# i2-mb_r1.net
KiCad netlist of a schematic drawn in EAGLE
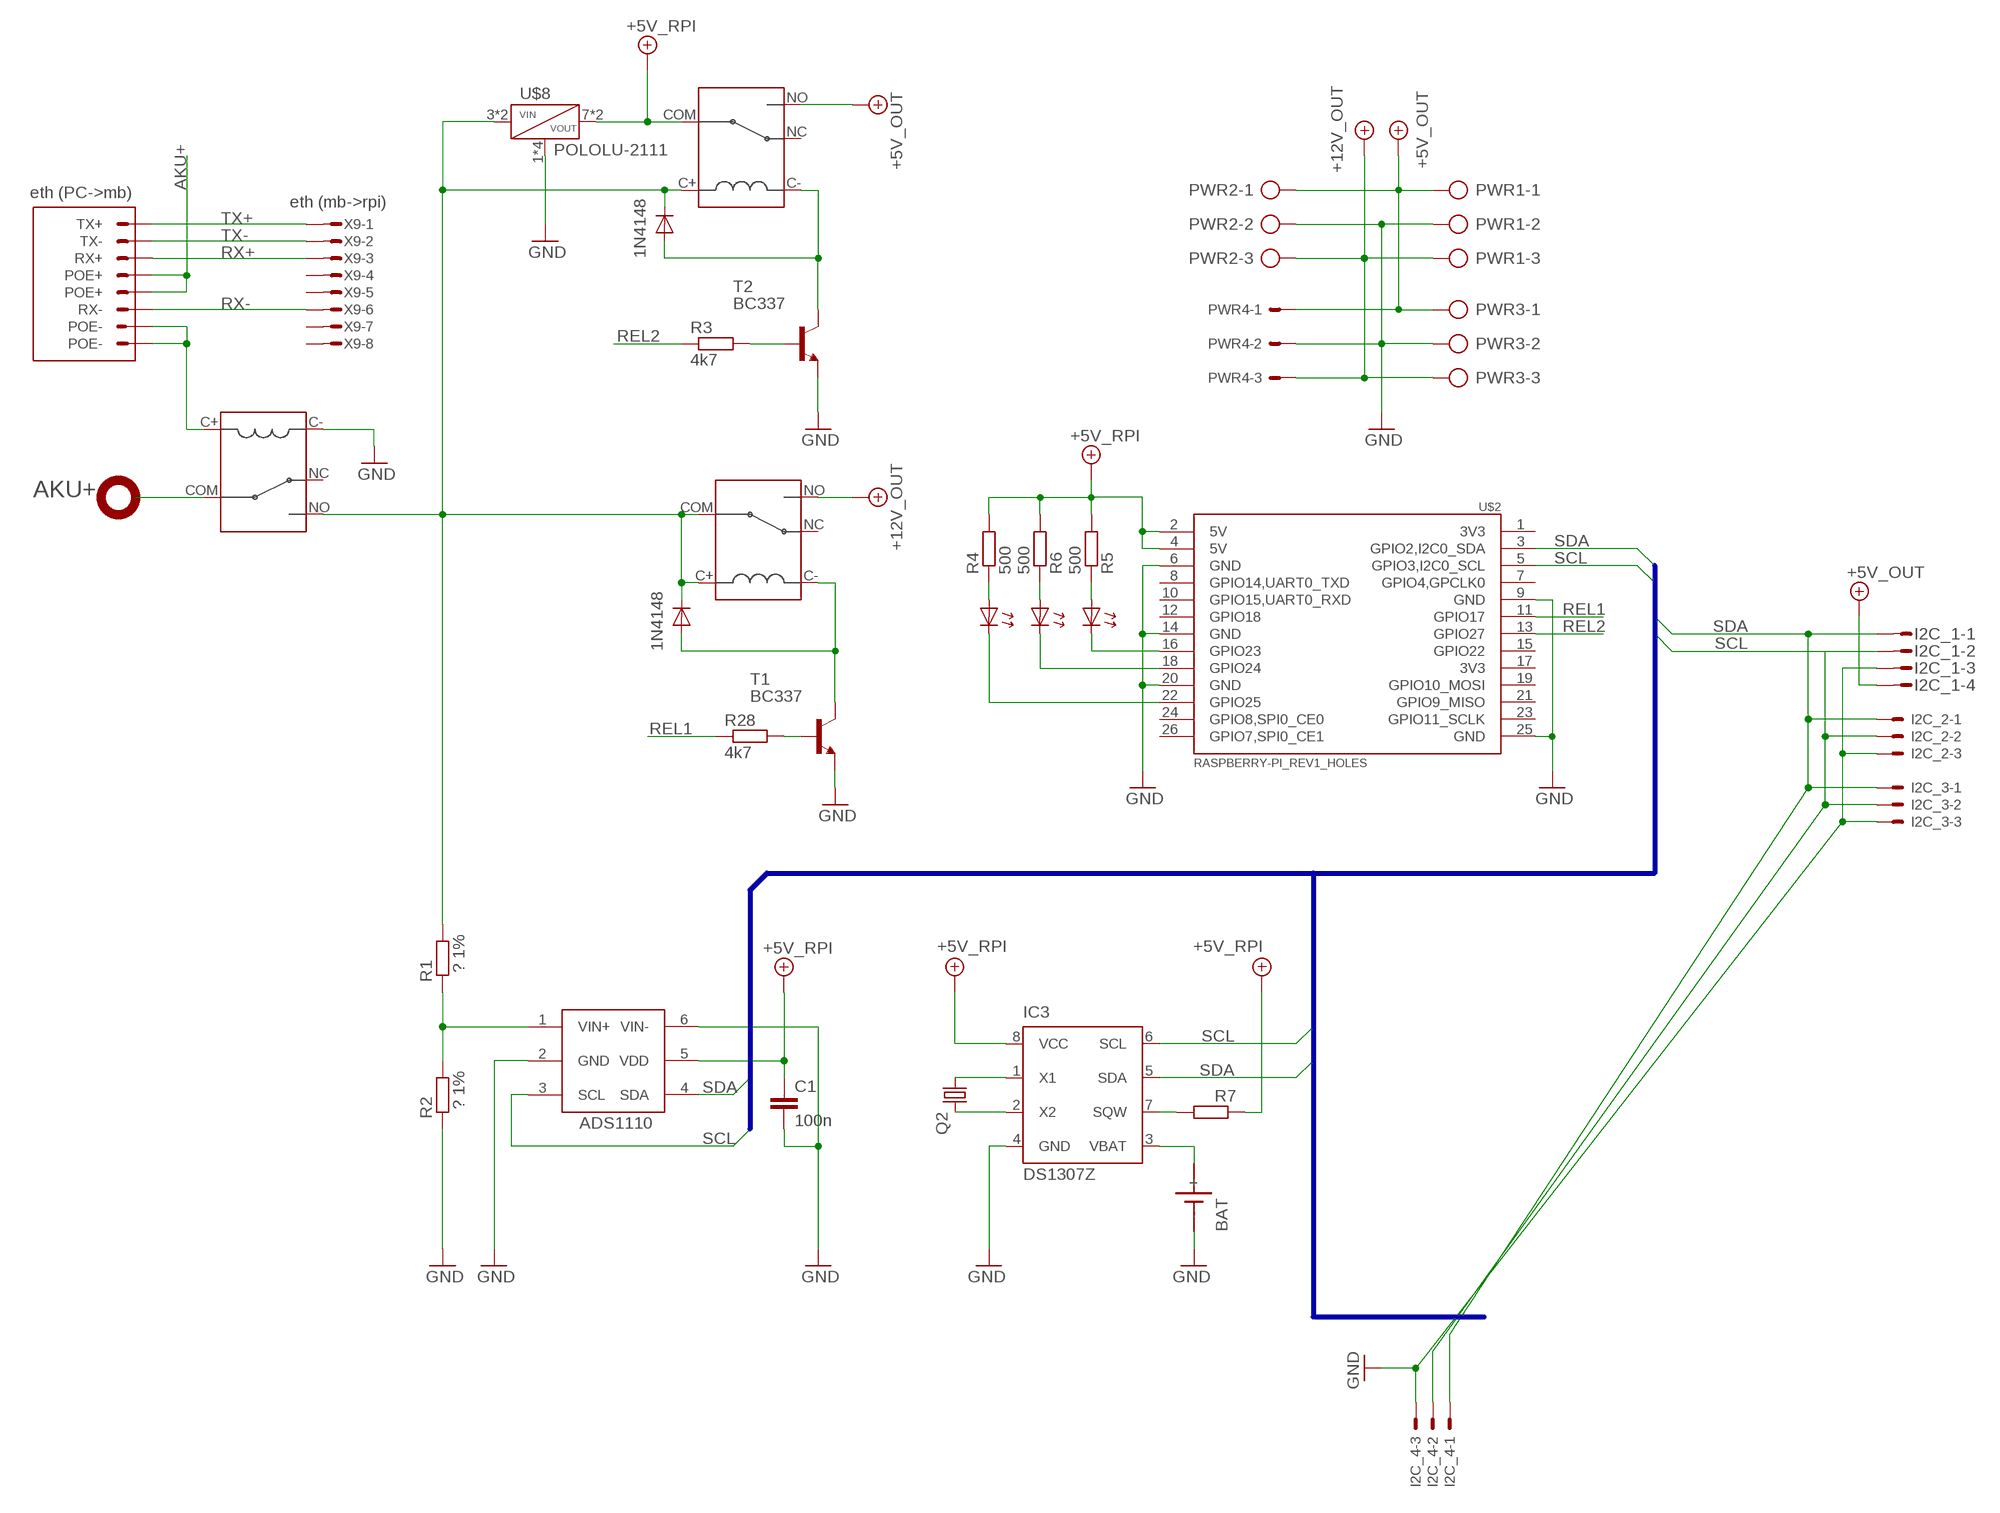
[diagram p0: schematic, sheet 1]

(export (version "E")
  (design (tool "Eeschema 10.0.6"))
  (components
    (comp (ref "BAT")
      (value "SN2032")
      (footprint "eagle-import:SN2032")
      (libsource (lib "eagle-import") (part "SN2032"))
    )
    (comp (ref "C1")
      (value "100n")
      (footprint "eagle-import:C0603")
      (libsource (lib "eagle-import") (part "C-EUC0603"))
    )
    (comp (ref "I2C_1")
      (value "MICROMATCH-4")
      (footprint "eagle-import:MICROMATCH-4")
      (fields (field (name "MPN") "7-215464-4"))
      (libsource (lib "eagle-import") (part "MICROMATCH-4"))
    )
    (comp (ref "I2C_2")
      (value "C-GRID-03-70553")
      (footprint "eagle-import:70553-03")
      (libsource (lib "eagle-import") (part "C-GRID-03-70553"))
    )
    (comp (ref "I2C_3")
      (value "C-GRID-03-70553")
      (footprint "eagle-import:70553-03")
      (libsource (lib "eagle-import") (part "C-GRID-03-70553"))
    )
    (comp (ref "I2C_4")
      (value "C-GRID-03-70553")
      (footprint "eagle-import:70553-03")
      (libsource (lib "eagle-import") (part "C-GRID-03-70553"))
    )
    (comp (ref "IC1")
      (value "ADS1110")
      (footprint "eagle-import:SOT-23-6")
      (libsource (lib "eagle-import") (part "ADS1110"))
    )
    (comp (ref "IC3")
      (value "DS1307Z")
      (footprint "eagle-import:SOIC8")
      (libsource (lib "eagle-import") (part "DS1307Z"))
    )
    (comp (ref "LED1")
      (value "LED0603")
      (footprint "eagle-import:D0603")
      (libsource (lib "eagle-import") (part "LED0603"))
    )
    (comp (ref "LED2")
      (value "LED0603")
      (footprint "eagle-import:D0603")
      (libsource (lib "eagle-import") (part "LED0603"))
    )
    (comp (ref "LED3")
      (value "LED0603")
      (footprint "eagle-import:D0603")
      (libsource (lib "eagle-import") (part "LED0603"))
    )
    (comp (ref "PWR1")
      (value "TBMP5103RC-KFV1")
      (footprint "eagle-import:TBMP5103RC-KF")
      (libsource (lib "eagle-import") (part "TBMP5103RC-KFV1"))
    )
    (comp (ref "PWR2")
      (value "TBMP5103RC-KFV1")
      (footprint "eagle-import:TBMP5103RC-KF")
      (libsource (lib "eagle-import") (part "TBMP5103RC-KFV1"))
    )
    (comp (ref "PWR3")
      (value "TBMP5103RC-KFV1")
      (footprint "eagle-import:TBMP5103RC-KF")
      (libsource (lib "eagle-import") (part "TBMP5103RC-KFV1"))
    )
    (comp (ref "PWR4")
      (value "C-GRID-03-70543")
      (footprint "eagle-import:70543-03")
      (libsource (lib "eagle-import") (part "C-GRID-03-70543"))
    )
    (comp (ref "Q2")
      (value "CRYSTAL")
      (footprint "eagle-import:CFPX-217")
      (libsource (lib "eagle-import") (part "CRYSTAL"))
    )
    (comp (ref "R1")
      (value "? 1%")
      (footprint "eagle-import:R0603")
      (libsource (lib "eagle-import") (part "R-EU_R0603"))
    )
    (comp (ref "R2")
      (value "? 1%")
      (footprint "eagle-import:R0603")
      (libsource (lib "eagle-import") (part "R-EU_R0603"))
    )
    (comp (ref "R3")
      (value "4k7")
      (footprint "eagle-import:R0603")
      (libsource (lib "eagle-import") (part "R-EU_R0603"))
    )
    (comp (ref "R4")
      (value "500")
      (footprint "eagle-import:R0603")
      (libsource (lib "eagle-import") (part "R-EU_R0603"))
    )
    (comp (ref "R5")
      (value "500")
      (footprint "eagle-import:R0603")
      (libsource (lib "eagle-import") (part "R-EU_R0603"))
    )
    (comp (ref "R6")
      (value "500")
      (footprint "eagle-import:R0603")
      (libsource (lib "eagle-import") (part "R-EU_R0603"))
    )
    (comp (ref "R7")
      (value "R-EU_R0603")
      (footprint "eagle-import:R0603")
      (libsource (lib "eagle-import") (part "R-EU_R0603"))
    )
    (comp (ref "R28")
      (value "4k7")
      (footprint "eagle-import:R0603")
      (libsource (lib "eagle-import") (part "R-EU_R0603"))
    )
    (comp (ref "T1")
      (value "BC337")
      (footprint "eagle-import:TO92")
      (libsource (lib "eagle-import") (part "BC337"))
    )
    (comp (ref "T2")
      (value "BC337")
      (footprint "eagle-import:TO92")
      (libsource (lib "eagle-import") (part "BC337"))
    )
    (comp (ref "U$2")
      (value "RASPBERRY-PI_REV1_HOLES")
      (footprint "eagle-import:RASPBERRY-PI_HOLES")
      (libsource (lib "eagle-import") (part "RASPBERRY-PI_REV1_HOLES"))
    )
    (comp (ref "U$3")
      (value "1N4148")
      (footprint "eagle-import:D0603")
      (libsource (lib "eagle-import") (part "D0603"))
    )
    (comp (ref "U$4")
      (value "1N4148")
      (footprint "eagle-import:D0603")
      (libsource (lib "eagle-import") (part "D0603"))
    )
    (comp (ref "U$5")
      (value "FBR51")
      (footprint "eagle-import:PC_RELAY")
      (libsource (lib "eagle-import") (part "FBR51"))
    )
    (comp (ref "U$6")
      (value "FBR51")
      (footprint "eagle-import:PC_RELAY")
      (libsource (lib "eagle-import") (part "FBR51"))
    )
    (comp (ref "U$7")
      (value "FBR51")
      (footprint "eagle-import:PC_RELAY")
      (libsource (lib "eagle-import") (part "FBR51"))
    )
    (comp (ref "U$8")
      (value "POLOLU-2111")
      (footprint "eagle-import:POLOLU-2111")
      (libsource (lib "eagle-import") (part "POLOLU-2111"))
    )
    (comp (ref "X9")
      (value "eth (mb->rpi)")
      (footprint "eagle-import:MICROMATCH-8")
      (libsource (lib "eagle-import") (part "MICROMATCH-8"))
    )
    (comp (ref "X_ETH")
      (value "eth (PC->mb)")
      (footprint "eagle-import:8P8C-TOP")
      (libsource (lib "eagle-import") (part "RJ45"))
    )
  )
  (nets
    (net (code "1") (name "+5V_OUT") (class "Default")
      (node (ref "I2C_1") (pin "4") (pinfunction "S_4") (pintype "passive"))
      (node (ref "PWR1") (pin "1") (pinfunction "P_1") (pintype "passive"))
      (node (ref "PWR2") (pin "1") (pinfunction "P_1") (pintype "passive"))
      (node (ref "PWR3") (pin "1") (pinfunction "P_1") (pintype "passive"))
      (node (ref "PWR4") (pin "1") (pinfunction "S_1") (pintype "passive"))
      (node (ref "U$5") (pin "NO") (pinfunction "NO_NO") (pintype "bidirectional"))
    )
    (net (code "2") (name "+5V_RPI") (class "Default")
      (node (ref "C1") (pin "1") (pinfunction "1_1") (pintype "passive"))
      (node (ref "IC1") (pin "5") (pinfunction "VDD_5") (pintype "bidirectional"))
      (node (ref "IC3") (pin "8") (pinfunction "VCC_8") (pintype "power_in"))
      (node (ref "R4") (pin "2") (pinfunction "2_2") (pintype "passive"))
      (node (ref "R5") (pin "2") (pinfunction "2_2") (pintype "passive"))
      (node (ref "R6") (pin "2") (pinfunction "2_2") (pintype "passive"))
      (node (ref "R7") (pin "1") (pinfunction "1_1") (pintype "passive"))
      (node (ref "U$2") (pin "2") (pinfunction "5V_2") (pintype "bidirectional"))
      (node (ref "U$2") (pin "4") (pinfunction "5V_4") (pintype "bidirectional"))
      (node (ref "U$5") (pin "COM") (pinfunction "COM_COM") (pintype "bidirectional"))
      (node (ref "U$8") (pin "7") (pinfunction "VOUT_7") (pintype "passive"))
      (node (ref "U$8") (pin "8") (pinfunction "VOUT_8") (pintype "passive"))
    )
    (net (code "3") (name "+12V_OUT") (class "Default")
      (node (ref "PWR1") (pin "3") (pinfunction "P_3") (pintype "passive"))
      (node (ref "PWR2") (pin "3") (pinfunction "P_3") (pintype "passive"))
      (node (ref "PWR3") (pin "3") (pinfunction "P_3") (pintype "passive"))
      (node (ref "PWR4") (pin "3") (pinfunction "S_3") (pintype "passive"))
      (node (ref "U$7") (pin "NO") (pinfunction "NO_NO") (pintype "bidirectional"))
    )
    (net (code "4") (name "/AKU+") (class "Default")
      (node (ref "U$6") (pin "COM") (pinfunction "COM_COM") (pintype "bidirectional"))
      (node (ref "X_ETH") (pin "4") (pinfunction "POE+_4") (pintype "bidirectional"))
      (node (ref "X_ETH") (pin "5") (pinfunction "POE+_5") (pintype "bidirectional"))
    )
    (net (code "5") (name "/REL1") (class "Default")
      (node (ref "R28") (pin "1") (pinfunction "1_1") (pintype "passive"))
      (node (ref "U$2") (pin "11") (pinfunction "GPIO17_11") (pintype "bidirectional"))
    )
    (net (code "6") (name "/REL2") (class "Default")
      (node (ref "R3") (pin "1") (pinfunction "1_1") (pintype "passive"))
      (node (ref "U$2") (pin "13") (pinfunction "GPIO27_13") (pintype "bidirectional"))
    )
    (net (code "7") (name "/RX+") (class "Default")
      (node (ref "X9") (pin "3") (pinfunction "S_3") (pintype "passive"))
      (node (ref "X_ETH") (pin "3") (pinfunction "RX+_3") (pintype "bidirectional"))
    )
    (net (code "8") (name "/RX-") (class "Default")
      (node (ref "X9") (pin "6") (pinfunction "S_6") (pintype "passive"))
      (node (ref "X_ETH") (pin "6") (pinfunction "RX-_6") (pintype "bidirectional"))
    )
    (net (code "9") (name "/SCL") (class "Default")
      (node (ref "I2C_1") (pin "2") (pinfunction "S_2") (pintype "passive"))
      (node (ref "I2C_2") (pin "2") (pinfunction "S_2") (pintype "passive"))
      (node (ref "I2C_3") (pin "2") (pinfunction "S_2") (pintype "passive"))
      (node (ref "I2C_4") (pin "2") (pinfunction "S_2") (pintype "passive"))
      (node (ref "IC1") (pin "3") (pinfunction "SCL_3") (pintype "bidirectional"))
      (node (ref "IC3") (pin "6") (pinfunction "SCL_6") (pintype "input"))
      (node (ref "U$2") (pin "5") (pinfunction "GPIO3,I2C0_SCL_5") (pintype "bidirectional"))
    )
    (net (code "10") (name "/SDA") (class "Default")
      (node (ref "I2C_1") (pin "1") (pinfunction "S_1") (pintype "passive"))
      (node (ref "I2C_2") (pin "1") (pinfunction "S_1") (pintype "passive"))
      (node (ref "I2C_3") (pin "1") (pinfunction "S_1") (pintype "passive"))
      (node (ref "I2C_4") (pin "1") (pinfunction "S_1") (pintype "passive"))
      (node (ref "IC1") (pin "4") (pinfunction "SDA_4") (pintype "bidirectional"))
      (node (ref "IC3") (pin "5") (pinfunction "SDA_5") (pintype "bidirectional"))
      (node (ref "U$2") (pin "3") (pinfunction "GPIO2,I2C0_SDA_3") (pintype "bidirectional"))
    )
    (net (code "11") (name "/TX+") (class "Default")
      (node (ref "X9") (pin "1") (pinfunction "S_1") (pintype "passive"))
      (node (ref "X_ETH") (pin "1") (pinfunction "TX+_1") (pintype "bidirectional"))
    )
    (net (code "12") (name "/TX-") (class "Default")
      (node (ref "X9") (pin "2") (pinfunction "S_2") (pintype "passive"))
      (node (ref "X_ETH") (pin "2") (pinfunction "TX-_2") (pintype "bidirectional"))
    )
    (net (code "13") (name "GND") (class "Default")
      (node (ref "BAT") (pin "-") (pinfunction "-_-") (pintype "passive"))
      (node (ref "C1") (pin "2") (pinfunction "2_2") (pintype "passive"))
      (node (ref "I2C_1") (pin "3") (pinfunction "S_3") (pintype "passive"))
      (node (ref "I2C_2") (pin "3") (pinfunction "S_3") (pintype "passive"))
      (node (ref "I2C_3") (pin "3") (pinfunction "S_3") (pintype "passive"))
      (node (ref "I2C_4") (pin "3") (pinfunction "S_3") (pintype "passive"))
      (node (ref "IC1") (pin "2") (pinfunction "GND_2") (pintype "bidirectional"))
      (node (ref "IC1") (pin "6") (pinfunction "VIN-_6") (pintype "bidirectional"))
      (node (ref "IC3") (pin "4") (pinfunction "GND_4") (pintype "power_in"))
      (node (ref "PWR1") (pin "2") (pinfunction "P_2") (pintype "passive"))
      (node (ref "PWR2") (pin "2") (pinfunction "P_2") (pintype "passive"))
      (node (ref "PWR3") (pin "2") (pinfunction "P_2") (pintype "passive"))
      (node (ref "PWR4") (pin "2") (pinfunction "S_2") (pintype "passive"))
      (node (ref "R2") (pin "2") (pinfunction "2_2") (pintype "passive"))
      (node (ref "T1") (pin "1") (pinfunction "E_1") (pintype "passive"))
      (node (ref "T2") (pin "1") (pinfunction "E_1") (pintype "passive"))
      (node (ref "U$2") (pin "14") (pinfunction "GND_14") (pintype "bidirectional"))
      (node (ref "U$2") (pin "20") (pinfunction "GND_20") (pintype "bidirectional"))
      (node (ref "U$2") (pin "25") (pinfunction "GND_25") (pintype "bidirectional"))
      (node (ref "U$2") (pin "6") (pinfunction "GND_6") (pintype "bidirectional"))
      (node (ref "U$2") (pin "9") (pinfunction "GND_9") (pintype "bidirectional"))
      (node (ref "U$6") (pin "C-") (pinfunction "C-_C-") (pintype "bidirectional"))
      (node (ref "U$8") (pin "1") (pinfunction "GND_1") (pintype "passive"))
      (node (ref "U$8") (pin "2") (pinfunction "GND_2") (pintype "passive"))
      (node (ref "U$8") (pin "5") (pinfunction "GND_5") (pintype "passive"))
      (node (ref "U$8") (pin "6") (pinfunction "GND_6") (pintype "passive"))
    )
    (net (code "14") (name "Net-(IC1-VIN+)") (class "Default")
      (node (ref "IC1") (pin "1") (pinfunction "VIN+_1") (pintype "bidirectional"))
      (node (ref "R1") (pin "2") (pinfunction "2_2") (pintype "passive"))
      (node (ref "R2") (pin "1") (pinfunction "1_1") (pintype "passive"))
    )
    (net (code "15") (name "Net-(IC3-SQW)") (class "Default")
      (node (ref "IC3") (pin "7") (pinfunction "SQW_7") (pintype "open_collector"))
      (node (ref "R7") (pin "2") (pinfunction "2_2") (pintype "passive"))
    )
    (net (code "16") (name "Net-(IC3-VBAT)") (class "Default")
      (node (ref "BAT") (pin "+") (pinfunction "+_+") (pintype "passive"))
      (node (ref "IC3") (pin "3") (pinfunction "VBAT_3") (pintype "passive"))
    )
    (net (code "17") (name "Net-(IC3-X1)") (class "Default")
      (node (ref "IC3") (pin "1") (pinfunction "X1_1") (pintype "input"))
      (node (ref "Q2") (pin "1") (pinfunction "1_1") (pintype "passive"))
    )
    (net (code "18") (name "Net-(IC3-X2)") (class "Default")
      (node (ref "IC3") (pin "2") (pinfunction "X2_2") (pintype "output"))
      (node (ref "Q2") (pin "2") (pinfunction "2_2") (pintype "passive"))
    )
    (net (code "19") (name "Net-(LED1-A)") (class "Default")
      (node (ref "LED1") (pin "1") (pinfunction "A_1") (pintype "passive"))
      (node (ref "R4") (pin "1") (pinfunction "1_1") (pintype "passive"))
    )
    (net (code "20") (name "Net-(LED1-C)") (class "Default")
      (node (ref "LED1") (pin "2") (pinfunction "C_2") (pintype "passive"))
      (node (ref "U$2") (pin "22") (pinfunction "GPIO25_22") (pintype "bidirectional"))
    )
    (net (code "21") (name "Net-(LED2-A)") (class "Default")
      (node (ref "LED2") (pin "1") (pinfunction "A_1") (pintype "passive"))
      (node (ref "R5") (pin "1") (pinfunction "1_1") (pintype "passive"))
    )
    (net (code "22") (name "Net-(LED2-C)") (class "Default")
      (node (ref "LED2") (pin "2") (pinfunction "C_2") (pintype "passive"))
      (node (ref "U$2") (pin "16") (pinfunction "GPIO23_16") (pintype "bidirectional"))
    )
    (net (code "23") (name "Net-(LED3-A)") (class "Default")
      (node (ref "LED3") (pin "1") (pinfunction "A_1") (pintype "passive"))
      (node (ref "R6") (pin "1") (pinfunction "1_1") (pintype "passive"))
    )
    (net (code "24") (name "Net-(LED3-C)") (class "Default")
      (node (ref "LED3") (pin "2") (pinfunction "C_2") (pintype "passive"))
      (node (ref "U$2") (pin "18") (pinfunction "GPIO24_18") (pintype "bidirectional"))
    )
    (net (code "25") (name "Net-(T1-B)") (class "Default")
      (node (ref "R28") (pin "2") (pinfunction "2_2") (pintype "passive"))
      (node (ref "T1") (pin "2") (pinfunction "B_2") (pintype "passive"))
    )
    (net (code "26") (name "Net-(T1-C)") (class "Default")
      (node (ref "T1") (pin "3") (pinfunction "C_3") (pintype "passive"))
      (node (ref "U$4") (pin "1") (pinfunction "A_1") (pintype "passive"))
      (node (ref "U$7") (pin "C-") (pinfunction "C-_C-") (pintype "bidirectional"))
    )
    (net (code "27") (name "Net-(T2-B)") (class "Default")
      (node (ref "R3") (pin "2") (pinfunction "2_2") (pintype "passive"))
      (node (ref "T2") (pin "2") (pinfunction "B_2") (pintype "passive"))
    )
    (net (code "28") (name "Net-(T2-C)") (class "Default")
      (node (ref "T2") (pin "3") (pinfunction "C_3") (pintype "passive"))
      (node (ref "U$3") (pin "1") (pinfunction "A_1") (pintype "passive"))
      (node (ref "U$5") (pin "C-") (pinfunction "C-_C-") (pintype "bidirectional"))
    )
    (net (code "29") (name "Net-(U$3-C)") (class "Default")
      (node (ref "R1") (pin "1") (pinfunction "1_1") (pintype "passive"))
      (node (ref "U$3") (pin "2") (pinfunction "C_2") (pintype "passive"))
      (node (ref "U$4") (pin "2") (pinfunction "C_2") (pintype "passive"))
      (node (ref "U$5") (pin "C+") (pinfunction "C+_C+") (pintype "bidirectional"))
      (node (ref "U$6") (pin "NO") (pinfunction "NO_NO") (pintype "bidirectional"))
      (node (ref "U$7") (pin "C+") (pinfunction "C+_C+") (pintype "bidirectional"))
      (node (ref "U$7") (pin "COM") (pinfunction "COM_COM") (pintype "bidirectional"))
      (node (ref "U$8") (pin "3") (pinfunction "VIN_3") (pintype "passive"))
      (node (ref "U$8") (pin "4") (pinfunction "VIN_4") (pintype "passive"))
    )
    (net (code "30") (name "Net-(U$6-PadC+)") (class "Default")
      (node (ref "U$6") (pin "C+") (pinfunction "C+_C+") (pintype "bidirectional"))
      (node (ref "X_ETH") (pin "7") (pinfunction "POE-_7") (pintype "bidirectional"))
      (node (ref "X_ETH") (pin "8") (pinfunction "POE-_8") (pintype "bidirectional"))
    )
    (net (code "31") (name "unconnected-(U$2-3V3-Pad1)") (class "Default")
      (node (ref "U$2") (pin "1") (pinfunction "3V3_1") (pintype "bidirectional"))
    )
    (net (code "32") (name "unconnected-(U$2-3V3-Pad17)") (class "Default")
      (node (ref "U$2") (pin "17") (pinfunction "3V3_17") (pintype "bidirectional"))
    )
    (net (code "33") (name "unconnected-(U$2-GPIO4,GPCLK0-Pad7)") (class "Default")
      (node (ref "U$2") (pin "7") (pinfunction "GPIO4,GPCLK0_7") (pintype "bidirectional"))
    )
    (net (code "34") (name "unconnected-(U$2-GPIO7,SPI0_CE1-Pad26)") (class "Default")
      (node (ref "U$2") (pin "26") (pinfunction "GPIO7,SPI0_CE1_26") (pintype "bidirectional"))
    )
    (net (code "35") (name "unconnected-(U$2-GPIO8,SPI0_CE0-Pad24)") (class "Default")
      (node (ref "U$2") (pin "24") (pinfunction "GPIO8,SPI0_CE0_24") (pintype "bidirectional"))
    )
    (net (code "36") (name "unconnected-(U$2-GPIO9_MISO-Pad21)") (class "Default")
      (node (ref "U$2") (pin "21") (pinfunction "GPIO9_MISO_21") (pintype "bidirectional"))
    )
    (net (code "37") (name "unconnected-(U$2-GPIO10_MOSI-Pad19)") (class "Default")
      (node (ref "U$2") (pin "19") (pinfunction "GPIO10_MOSI_19") (pintype "bidirectional"))
    )
    (net (code "38") (name "unconnected-(U$2-GPIO11_SCLK-Pad23)") (class "Default")
      (node (ref "U$2") (pin "23") (pinfunction "GPIO11_SCLK_23") (pintype "bidirectional"))
    )
    (net (code "39") (name "unconnected-(U$2-GPIO14,UART0_TXD-Pad8)") (class "Default")
      (node (ref "U$2") (pin "8") (pinfunction "GPIO14,UART0_TXD_8") (pintype "bidirectional"))
    )
    (net (code "40") (name "unconnected-(U$2-GPIO15,UART0_RXD-Pad10)") (class "Default")
      (node (ref "U$2") (pin "10") (pinfunction "GPIO15,UART0_RXD_10") (pintype "bidirectional"))
    )
    (net (code "41") (name "unconnected-(U$2-GPIO18-Pad12)") (class "Default")
      (node (ref "U$2") (pin "12") (pinfunction "GPIO18_12") (pintype "bidirectional"))
    )
    (net (code "42") (name "unconnected-(U$2-GPIO22-Pad15)") (class "Default")
      (node (ref "U$2") (pin "15") (pinfunction "GPIO22_15") (pintype "bidirectional"))
    )
    (net (code "43") (name "unconnected-(U$5-PadNC)") (class "Default")
      (node (ref "U$5") (pin "NC") (pinfunction "NC_NC") (pintype "bidirectional"))
    )
    (net (code "44") (name "unconnected-(U$6-PadNC)") (class "Default")
      (node (ref "U$6") (pin "NC") (pinfunction "NC_NC") (pintype "bidirectional"))
    )
    (net (code "45") (name "unconnected-(U$7-PadNC)") (class "Default")
      (node (ref "U$7") (pin "NC") (pinfunction "NC_NC") (pintype "bidirectional"))
    )
    (net (code "46") (name "unconnected-(X9D-S-Pad4)") (class "Default")
      (node (ref "X9") (pin "4") (pinfunction "S_4") (pintype "passive"))
    )
    (net (code "47") (name "unconnected-(X9E-S-Pad5)") (class "Default")
      (node (ref "X9") (pin "5") (pinfunction "S_5") (pintype "passive"))
    )
    (net (code "48") (name "unconnected-(X9G-S-Pad7)") (class "Default")
      (node (ref "X9") (pin "7") (pinfunction "S_7") (pintype "passive"))
    )
    (net (code "49") (name "unconnected-(X9H-S-Pad8)") (class "Default")
      (node (ref "X9") (pin "8") (pinfunction "S_8") (pintype "passive"))
    )
  )
)
